# chirp-v2_4.net
KiCad netlist of a schematic drawn in EAGLE
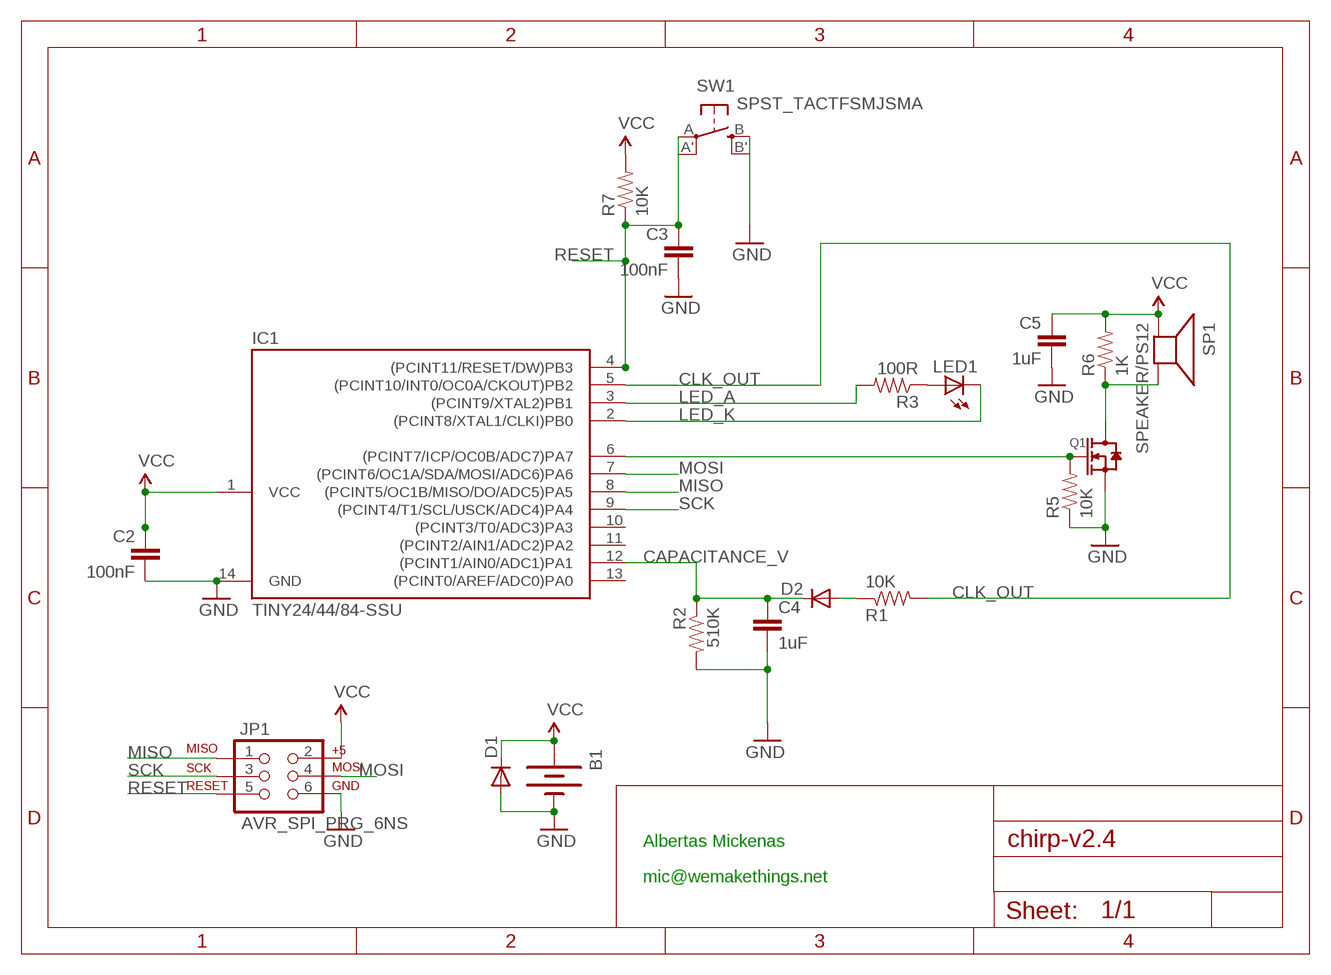
[diagram p0: schematic, sheet 1]

(export (version "E")
  (design (tool "Eeschema 10.0.6"))
  (components
    (comp (ref "B1")
      (value "BATTERY")
      (footprint "eagle-import:BAT-HLD-001")
      (libsource (lib "eagle-import") (part "BATTERY"))
    )
    (comp (ref "C2")
      (value "100nF")
      (footprint "eagle-import:0603-CAP")
      (libsource (lib "eagle-import") (part "CAP0603-CAP"))
    )
    (comp (ref "C3")
      (value "100nF")
      (footprint "eagle-import:0603-CAP")
      (libsource (lib "eagle-import") (part "CAP0603-CAP"))
    )
    (comp (ref "C4")
      (value "1uF")
      (footprint "eagle-import:0603-CAP")
      (libsource (lib "eagle-import") (part "CAP0603-CAP"))
    )
    (comp (ref "C5")
      (value "1uF")
      (footprint "eagle-import:0603-CAP")
      (libsource (lib "eagle-import") (part "CAP0603-CAP"))
    )
    (comp (ref "D1")
      (value "DIODE-DO214AC")
      (footprint "eagle-import:DO214AC")
      (libsource (lib "eagle-import") (part "DIODE-DO214AC"))
    )
    (comp (ref "D2")
      (value "DIODE-SCHOTTKY_")
      (footprint "eagle-import:SOD-523")
      (libsource (lib "eagle-import") (part "DIODESOD-523"))
    )
    (comp (ref "IC1")
      (value "TINY24/44/84-SSU")
      (footprint "eagle-import:SOIC14")
      (libsource (lib "eagle-import") (part "TINY24/44/84-SSU"))
    )
    (comp (ref "JP1")
      (value "AVR_SPI_PRG_6NS")
      (footprint "eagle-import:2X3-NS")
      (libsource (lib "eagle-import") (part "AVR_SPI_PRG_6NS"))
    )
    (comp (ref "LED1")
      (value "LEDCHIPLED_0805")
      (footprint "eagle-import:CHIPLED_0805")
      (libsource (lib "eagle-import") (part "LEDCHIPLED_0805"))
    )
    (comp (ref "Q1")
      (value "MOSFET-N-SOT23")
      (footprint "eagle-import:SOT23")
      (libsource (lib "eagle-import") (part "MOSFET-N-SOT23"))
    )
    (comp (ref "R1")
      (value "10K")
      (footprint "eagle-import:0603-RES")
      (libsource (lib "eagle-import") (part "RESISTOR0603-RES"))
    )
    (comp (ref "R2")
      (value "510K")
      (footprint "eagle-import:0603-RES")
      (libsource (lib "eagle-import") (part "RESISTOR0603-RES"))
    )
    (comp (ref "R3")
      (value "100R")
      (footprint "eagle-import:0603-RES")
      (libsource (lib "eagle-import") (part "RESISTOR0603-RES"))
    )
    (comp (ref "R5")
      (value "10K")
      (footprint "eagle-import:0603-RES")
      (libsource (lib "eagle-import") (part "RESISTOR0603-RES"))
    )
    (comp (ref "R6")
      (value "1K")
      (footprint "eagle-import:0603-RES")
      (libsource (lib "eagle-import") (part "RESISTOR0603-RES"))
    )
    (comp (ref "R7")
      (value "10K")
      (footprint "eagle-import:0603-RES")
      (libsource (lib "eagle-import") (part "RESISTOR0603-RES"))
    )
    (comp (ref "SP1")
      (value "SPEAKER/PS12")
      (footprint "eagle-import:PS12")
      (libsource (lib "eagle-import") (part "SPEAKER/PS12"))
    )
    (comp (ref "SW1")
      (value "SPST_TACTFSMJSMA")
      (footprint "eagle-import:FSMJSMA")
      (libsource (lib "eagle-import") (part "SPST_TACTFSMJSMA"))
    )
  )
  (nets
    (net (code "1") (name "/CAPACITANCE_V") (class "Default")
      (node (ref "C4") (pin "1") (pinfunction "1_1") (pintype "passive"))
      (node (ref "D2") (pin "K") (pinfunction "C_K") (pintype "passive"))
      (node (ref "IC1") (pin "12") (pinfunction "(PCINT1/AIN0/ADC1)PA1_12") (pintype "bidirectional"))
      (node (ref "R2") (pin "1") (pinfunction "1_1") (pintype "passive"))
    )
    (net (code "2") (name "/CLK_OUT") (class "Default")
      (node (ref "IC1") (pin "5") (pinfunction "(PCINT10/INT0/OC0A/CKOUT)PB2_5") (pintype "bidirectional"))
      (node (ref "R1") (pin "2") (pinfunction "2_2") (pintype "passive"))
    )
    (net (code "3") (name "/LED_A") (class "Default")
      (node (ref "IC1") (pin "3") (pinfunction "(PCINT9/XTAL2)PB1_3") (pintype "bidirectional"))
      (node (ref "R3") (pin "2") (pinfunction "2_2") (pintype "passive"))
    )
    (net (code "4") (name "/LED_K") (class "Default")
      (node (ref "IC1") (pin "2") (pinfunction "(PCINT8/XTAL1/CLKI)PB0_2") (pintype "bidirectional"))
      (node (ref "LED1") (pin "C") (pinfunction "C_C") (pintype "passive"))
    )
    (net (code "5") (name "/MISO") (class "Default")
      (node (ref "IC1") (pin "8") (pinfunction "(PCINT5/OC1B/MISO/DO/ADC5)PA5_8") (pintype "bidirectional"))
      (node (ref "JP1") (pin "1") (pinfunction "1_1") (pintype "passive"))
    )
    (net (code "6") (name "/MOSI") (class "Default")
      (node (ref "IC1") (pin "7") (pinfunction "(PCINT6/OC1A/SDA/MOSI/ADC6)PA6_7") (pintype "bidirectional"))
      (node (ref "JP1") (pin "4") (pinfunction "4_4") (pintype "passive"))
    )
    (net (code "7") (name "/RESET") (class "Default")
      (node (ref "C3") (pin "1") (pinfunction "1_1") (pintype "passive"))
      (node (ref "IC1") (pin "4") (pinfunction "(PCINT11/RESET/DW)PB3_4") (pintype "bidirectional"))
      (node (ref "JP1") (pin "5") (pinfunction "5_5") (pintype "passive"))
      (node (ref "R7") (pin "1") (pinfunction "1_1") (pintype "passive"))
      (node (ref "SW1") (pin "A") (pinfunction "P_A") (pintype "passive"))
      (node (ref "SW1") (pin "A'") (pinfunction "P1_A'") (pintype "passive"))
    )
    (net (code "8") (name "/SCK") (class "Default")
      (node (ref "IC1") (pin "9") (pinfunction "(PCINT4/T1/SCL/USCK/ADC4)PA4_9") (pintype "bidirectional"))
      (node (ref "JP1") (pin "3") (pinfunction "3_3") (pintype "passive"))
    )
    (net (code "9") (name "GND") (class "Default")
      (node (ref "B1") (pin "2") (pinfunction "-_2") (pintype "power_in"))
      (node (ref "C2") (pin "2") (pinfunction "2_2") (pintype "passive"))
      (node (ref "C3") (pin "2") (pinfunction "2_2") (pintype "passive"))
      (node (ref "C4") (pin "2") (pinfunction "2_2") (pintype "passive"))
      (node (ref "C5") (pin "2") (pinfunction "2_2") (pintype "passive"))
      (node (ref "D1") (pin "A") (pinfunction "A_A") (pintype "passive"))
      (node (ref "IC1") (pin "14") (pinfunction "GND_14") (pintype "power_in"))
      (node (ref "JP1") (pin "6") (pinfunction "6_6") (pintype "passive"))
      (node (ref "Q1") (pin "2") (pinfunction "S_2") (pintype "passive"))
      (node (ref "R2") (pin "2") (pinfunction "2_2") (pintype "passive"))
      (node (ref "R5") (pin "1") (pinfunction "1_1") (pintype "passive"))
      (node (ref "SW1") (pin "B") (pinfunction "S_B") (pintype "passive"))
      (node (ref "SW1") (pin "B'") (pinfunction "S1_B'") (pintype "passive"))
    )
    (net (code "10") (name "Net-(D2-PadA)") (class "Default")
      (node (ref "D2") (pin "A") (pinfunction "A_A") (pintype "passive"))
      (node (ref "R1") (pin "1") (pinfunction "1_1") (pintype "passive"))
    )
    (net (code "11") (name "Net-(IC1-(PCINT7{slash}ICP{slash}OC0B{slash}ADC7)PA7)") (class "Default")
      (node (ref "IC1") (pin "6") (pinfunction "(PCINT7/ICP/OC0B/ADC7)PA7_6") (pintype "bidirectional"))
      (node (ref "Q1") (pin "1") (pinfunction "G_1") (pintype "passive"))
      (node (ref "R5") (pin "2") (pinfunction "2_2") (pintype "passive"))
    )
    (net (code "12") (name "Net-(LED1-PadA)") (class "Default")
      (node (ref "LED1") (pin "A") (pinfunction "A_A") (pintype "passive"))
      (node (ref "R3") (pin "1") (pinfunction "1_1") (pintype "passive"))
    )
    (net (code "13") (name "Net-(Q1-D)") (class "Default")
      (node (ref "Q1") (pin "3") (pinfunction "D_3") (pintype "passive"))
      (node (ref "R6") (pin "1") (pinfunction "1_1") (pintype "passive"))
      (node (ref "SP1") (pin "P$2") (pinfunction "-_P$2") (pintype "passive"))
    )
    (net (code "14") (name "VCC") (class "Default")
      (node (ref "B1") (pin "1") (pinfunction "+_1") (pintype "power_in"))
      (node (ref "C2") (pin "1") (pinfunction "1_1") (pintype "passive"))
      (node (ref "C5") (pin "1") (pinfunction "1_1") (pintype "passive"))
      (node (ref "D1") (pin "C") (pinfunction "C_C") (pintype "passive"))
      (node (ref "IC1") (pin "1") (pinfunction "VCC_1") (pintype "power_in"))
      (node (ref "JP1") (pin "2") (pinfunction "2_2") (pintype "passive"))
      (node (ref "R6") (pin "2") (pinfunction "2_2") (pintype "passive"))
      (node (ref "R7") (pin "2") (pinfunction "2_2") (pintype "passive"))
      (node (ref "SP1") (pin "P$1") (pinfunction "+_P$1") (pintype "passive"))
    )
    (net (code "15") (name "unconnected-(IC1-(PCINT0{slash}AREF{slash}ADC0)PA0-Pad13)") (class "Default")
      (node (ref "IC1") (pin "13") (pinfunction "(PCINT0/AREF/ADC0)PA0_13") (pintype "bidirectional"))
    )
    (net (code "16") (name "unconnected-(IC1-(PCINT2{slash}AIN1{slash}ADC2)PA2-Pad11)") (class "Default")
      (node (ref "IC1") (pin "11") (pinfunction "(PCINT2/AIN1/ADC2)PA2_11") (pintype "bidirectional"))
    )
    (net (code "17") (name "unconnected-(IC1-(PCINT3{slash}T0{slash}ADC3)PA3-Pad10)") (class "Default")
      (node (ref "IC1") (pin "10") (pinfunction "(PCINT3/T0/ADC3)PA3_10") (pintype "bidirectional"))
    )
  )
)
